# BufAmp.net
KiCad netlist of a schematic drawn in Altium Designer
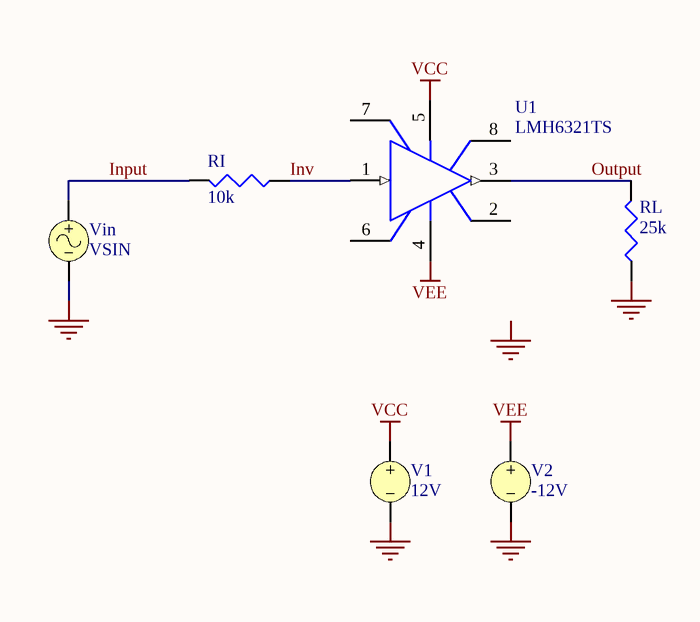
[diagram p0: BufAmp.schdoc]

(export (version "E")
  (design (tool "Eeschema 10.0.6"))
  (components
    (comp (ref "RI") (value "10k") (description "Resistor") (libsource (lib "") (part "RES_1")))
    (comp (ref "RL") (value "25k") (description "Resistor") (libsource (lib "*") (part "RES")))
    (comp (ref "U1")
      (value "LMH6321TS")
      (footprint "TS7B_N")
      (description "300 mA High Speed Buffer with Adjustable Current Limit")
      (fields
        (field (name "MANUFACTURER") "National Semiconductor")
        (field (name "DIGIKEYPARTNUMBER") "LMH6321TS-ND")
        (field (name "PUBLISHER") "Altium Limited")
      )
      (libsource (lib "NSC Amplifier with SIM models") (part "LMH6321TS"))
    )
    (comp (ref "V1") (value "12V") (description "Voltage Source") (libsource (lib "*") (part "VSRC")))
    (comp (ref "V2") (value "-12V") (description "Voltage Source") (libsource (lib "*") (part "VSRC")))
    (comp (ref "Vin")
      (value "VSIN")
      (description "Sinusoidal Voltage Source")
      (libsource (lib "*") (part "VSIN"))
    )
  )
  (nets
    (net (code "1") (name "/Input") (class "Default")
      (node (ref "RI") (pin "1") (pinfunction "TOP_1") (pintype "passive"))
      (node (ref "Vin") (pin "1") (pinfunction "1_1") (pintype "passive"))
    )
    (net (code "2") (name "/Inv") (class "Default")
      (node (ref "RI") (pin "2") (pinfunction "BOT_2") (pintype "passive"))
      (node (ref "U1") (pin "1") (pinfunction "IN_1") (pintype "input"))
    )
    (net (code "3") (name "/Output") (class "Default")
      (node (ref "RL") (pin "1") (pinfunction "TOP_1") (pintype "passive"))
      (node (ref "U1") (pin "3") (pinfunction "OUT_3") (pintype "output"))
    )
    (net (code "4") (name "GND") (class "Default")
      (node (ref "RL") (pin "2") (pinfunction "BOT_2") (pintype "passive"))
      (node (ref "V1") (pin "2") (pinfunction "2_2") (pintype "passive"))
      (node (ref "V2") (pin "2") (pinfunction "2_2") (pintype "passive"))
      (node (ref "Vin") (pin "2") (pinfunction "2_2") (pintype "passive"))
    )
    (net (code "5") (name "VCC") (class "Default")
      (node (ref "U1") (pin "5") (pinfunction "V+_5") (pintype "power_in"))
      (node (ref "V1") (pin "1") (pinfunction "1_1") (pintype "passive"))
    )
    (net (code "6") (name "VEE") (class "Default")
      (node (ref "U1") (pin "4") (pinfunction "V-_4") (pintype "power_in"))
      (node (ref "V2") (pin "1") (pinfunction "1_1") (pintype "passive"))
    )
    (net (code "7") (name "unconnected-(U1-CL-Pad7)") (class "Default")
      (node (ref "U1") (pin "7") (pinfunction "CL_7") (pintype "passive"))
    )
    (net (code "8") (name "unconnected-(U1-DAP-Pad8)") (class "Default")
      (node (ref "U1") (pin "8") (pinfunction "DAP_8") (pintype "passive"))
    )
    (net (code "9") (name "unconnected-(U1-EF-Pad6)") (class "Default")
      (node (ref "U1") (pin "6") (pinfunction "EF_6") (pintype "passive"))
    )
    (net (code "10") (name "unconnected-(U1-GND-Pad2)") (class "Default")
      (node (ref "U1") (pin "2") (pinfunction "GND_2") (pintype "power_in"))
    )
  )
)
